# untitled.net
KiCad netlist of a schematic drawn in EAGLE
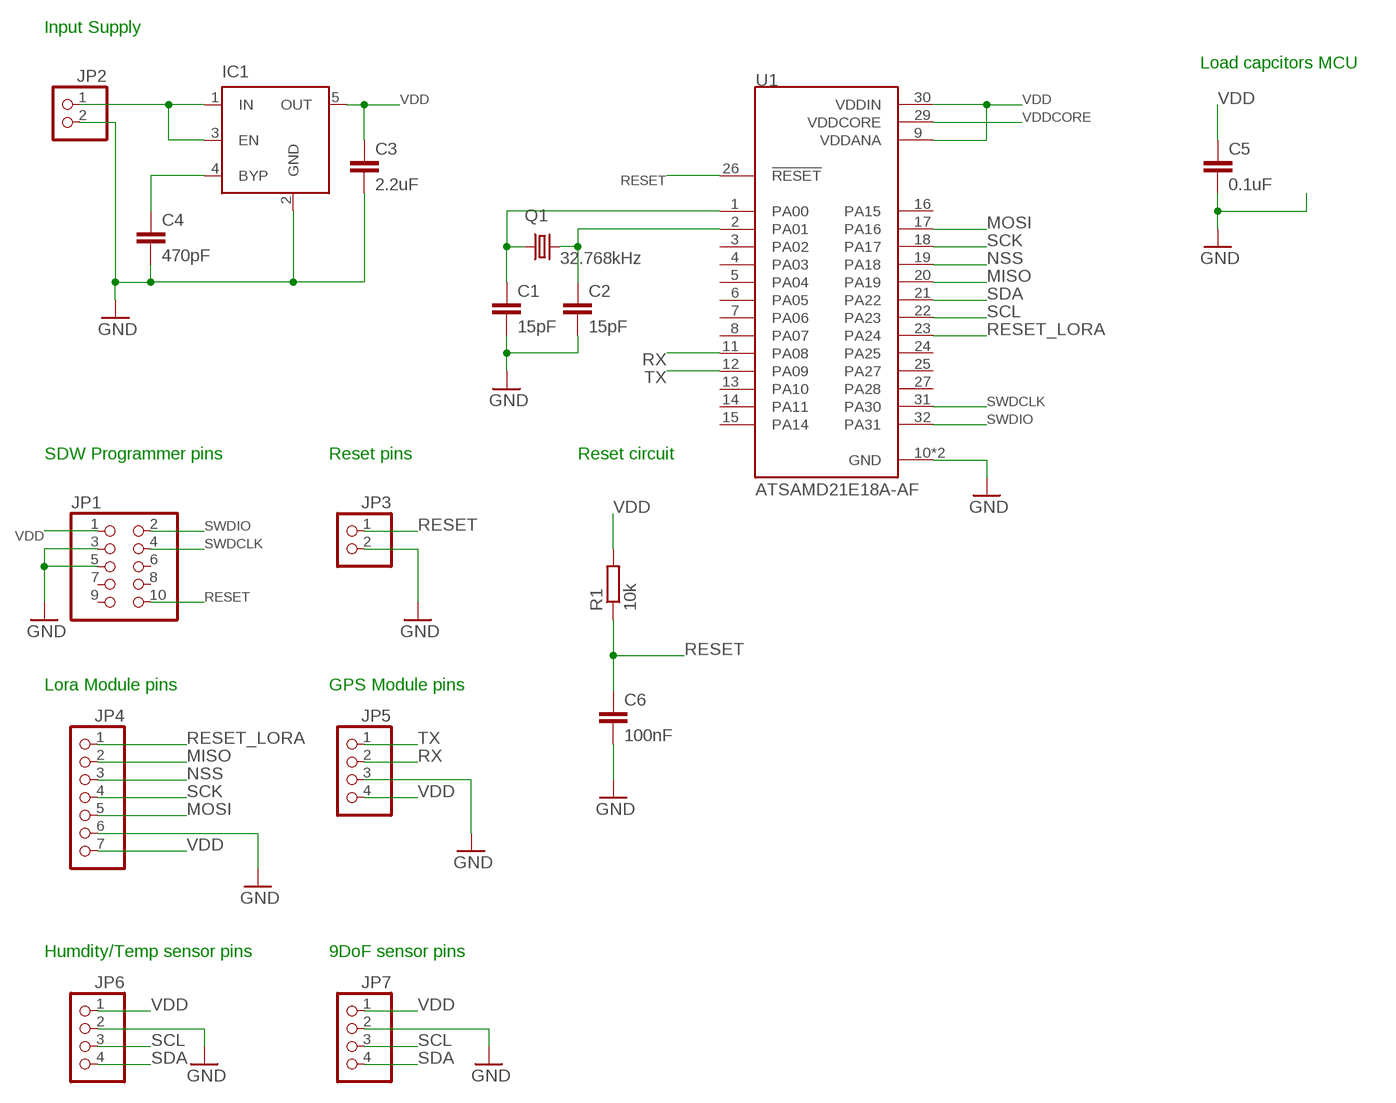
[diagram p0: schematic, sheet 1]

(export (version "E")
  (design (tool "Eeschema 10.0.6"))
  (components
    (comp (ref "C1")
      (value "15pF")
      (footprint "eagle-import:C0805")
      (libsource (lib "eagle-import") (part "C-EUC0805"))
    )
    (comp (ref "C2")
      (value "15pF")
      (footprint "eagle-import:C0805")
      (libsource (lib "eagle-import") (part "C-EUC0805"))
    )
    (comp (ref "C3")
      (value "2.2uF")
      (footprint "eagle-import:C0805")
      (libsource (lib "eagle-import") (part "C-EUC0805"))
    )
    (comp (ref "C4")
      (value "470pF")
      (footprint "eagle-import:C0805")
      (libsource (lib "eagle-import") (part "C-EUC0805"))
    )
    (comp (ref "C5")
      (value "0.1uF")
      (footprint "eagle-import:C0805")
      (libsource (lib "eagle-import") (part "C-EUC0805"))
    )
    (comp (ref "C6")
      (value "100nF")
      (footprint "eagle-import:C0805")
      (libsource (lib "eagle-import") (part "C-EUC0805"))
    )
    (comp (ref "IC1")
      (value "MIC5219XX")
      (footprint "eagle-import:SOT23-5")
      (libsource (lib "eagle-import") (part "MIC5219XX"))
    )
    (comp (ref "JP1")
      (value "PINHD-2X5")
      (footprint "eagle-import:2X05")
      (libsource (lib "eagle-import") (part "PINHD-2X5"))
    )
    (comp (ref "JP2")
      (value "PINHD-1X2")
      (footprint "eagle-import:1X02")
      (libsource (lib "eagle-import") (part "PINHD-1X2"))
    )
    (comp (ref "JP3")
      (value "PINHD-1X2")
      (footprint "eagle-import:1X02")
      (libsource (lib "eagle-import") (part "PINHD-1X2"))
    )
    (comp (ref "JP4")
      (value "PINHD-1X7")
      (footprint "eagle-import:1X07")
      (libsource (lib "eagle-import") (part "PINHD-1X7"))
    )
    (comp (ref "JP5")
      (value "PINHD-1X4")
      (footprint "eagle-import:1X04")
      (libsource (lib "eagle-import") (part "PINHD-1X4"))
    )
    (comp (ref "JP6")
      (value "PINHD-1X4")
      (footprint "eagle-import:1X04")
      (libsource (lib "eagle-import") (part "PINHD-1X4"))
    )
    (comp (ref "JP7")
      (value "PINHD-1X4")
      (footprint "eagle-import:1X04")
      (libsource (lib "eagle-import") (part "PINHD-1X4"))
    )
    (comp (ref "Q1")
      (value "32.768kHz")
      (footprint "eagle-import:CTS406")
      (libsource (lib "eagle-import") (part "CRYSTALCTS406"))
    )
    (comp (ref "R1")
      (value "10k")
      (footprint "eagle-import:R0805")
      (libsource (lib "eagle-import") (part "R-EU_R0805"))
    )
    (comp (ref "U1")
      (value "ATSAMD21E18A-AF")
      (footprint "eagle-import:QFP80P900X900X120-32N")
      (fields (field (name "MF") "Microchip"))
      (libsource (lib "eagle-import") (part "ATSAMD21E18A-AF"))
    )
  )
  (nets
    (net (code "1") (name "/MISO") (class "Default")
      (node (ref "JP4") (pin "2") (pinfunction "2_2") (pintype "passive"))
      (node (ref "U1") (pin "20") (pinfunction "PA19_20") (pintype "bidirectional"))
    )
    (net (code "2") (name "/MOSI") (class "Default")
      (node (ref "JP4") (pin "5") (pinfunction "5_5") (pintype "passive"))
      (node (ref "U1") (pin "17") (pinfunction "PA16_17") (pintype "bidirectional"))
    )
    (net (code "3") (name "/NSS") (class "Default")
      (node (ref "JP4") (pin "3") (pinfunction "3_3") (pintype "passive"))
      (node (ref "U1") (pin "19") (pinfunction "PA18_19") (pintype "bidirectional"))
    )
    (net (code "4") (name "/RESET") (class "Default")
      (node (ref "C6") (pin "1") (pinfunction "1_1") (pintype "passive"))
      (node (ref "JP1") (pin "10") (pinfunction "10_10") (pintype "passive"))
      (node (ref "JP3") (pin "1") (pinfunction "1_1") (pintype "passive"))
      (node (ref "R1") (pin "1") (pinfunction "1_1") (pintype "passive"))
      (node (ref "U1") (pin "26") (pinfunction "~{RESET}_26") (pintype "input"))
    )
    (net (code "5") (name "/RESET_LORA") (class "Default")
      (node (ref "JP4") (pin "1") (pinfunction "1_1") (pintype "passive"))
      (node (ref "U1") (pin "23") (pinfunction "PA24_23") (pintype "bidirectional"))
    )
    (net (code "6") (name "/RX") (class "Default")
      (node (ref "JP5") (pin "2") (pinfunction "2_2") (pintype "passive"))
      (node (ref "U1") (pin "11") (pinfunction "PA08_11") (pintype "bidirectional"))
    )
    (net (code "7") (name "/SCK") (class "Default")
      (node (ref "JP4") (pin "4") (pinfunction "4_4") (pintype "passive"))
      (node (ref "U1") (pin "18") (pinfunction "PA17_18") (pintype "bidirectional"))
    )
    (net (code "8") (name "/SCL") (class "Default")
      (node (ref "JP6") (pin "3") (pinfunction "3_3") (pintype "passive"))
      (node (ref "JP7") (pin "3") (pinfunction "3_3") (pintype "passive"))
      (node (ref "U1") (pin "22") (pinfunction "PA23_22") (pintype "bidirectional"))
    )
    (net (code "9") (name "/SDA") (class "Default")
      (node (ref "JP6") (pin "4") (pinfunction "4_4") (pintype "passive"))
      (node (ref "JP7") (pin "4") (pinfunction "4_4") (pintype "passive"))
      (node (ref "U1") (pin "21") (pinfunction "PA22_21") (pintype "bidirectional"))
    )
    (net (code "10") (name "/SWDCLK") (class "Default")
      (node (ref "JP1") (pin "4") (pinfunction "4_4") (pintype "passive"))
      (node (ref "U1") (pin "31") (pinfunction "PA30_31") (pintype "bidirectional"))
    )
    (net (code "11") (name "/SWDIO") (class "Default")
      (node (ref "JP1") (pin "2") (pinfunction "2_2") (pintype "passive"))
      (node (ref "U1") (pin "32") (pinfunction "PA31_32") (pintype "bidirectional"))
    )
    (net (code "12") (name "/TX") (class "Default")
      (node (ref "JP5") (pin "1") (pinfunction "1_1") (pintype "passive"))
      (node (ref "U1") (pin "12") (pinfunction "PA09_12") (pintype "bidirectional"))
    )
    (net (code "13") (name "/VDD") (class "Default")
      (node (ref "C3") (pin "1") (pinfunction "1_1") (pintype "passive"))
      (node (ref "C5") (pin "1") (pinfunction "1_1") (pintype "passive"))
      (node (ref "IC1") (pin "5") (pinfunction "OUT_5") (pintype "output"))
      (node (ref "JP1") (pin "1") (pinfunction "1_1") (pintype "passive"))
      (node (ref "JP4") (pin "7") (pinfunction "7_7") (pintype "passive"))
      (node (ref "JP5") (pin "4") (pinfunction "4_4") (pintype "passive"))
      (node (ref "JP6") (pin "1") (pinfunction "1_1") (pintype "passive"))
      (node (ref "JP7") (pin "1") (pinfunction "1_1") (pintype "passive"))
      (node (ref "R1") (pin "2") (pinfunction "2_2") (pintype "passive"))
      (node (ref "U1") (pin "30") (pinfunction "VDDIN_30") (pintype "power_in"))
      (node (ref "U1") (pin "9") (pinfunction "VDDANA_9") (pintype "power_in"))
    )
    (net (code "14") (name "/VDDCORE") (class "Default")
      (node (ref "U1") (pin "29") (pinfunction "VDDCORE_29") (pintype "power_in"))
    )
    (net (code "15") (name "GND") (class "Default")
      (node (ref "C1") (pin "2") (pinfunction "2_2") (pintype "passive"))
      (node (ref "C2") (pin "2") (pinfunction "2_2") (pintype "passive"))
      (node (ref "C3") (pin "2") (pinfunction "2_2") (pintype "passive"))
      (node (ref "C4") (pin "2") (pinfunction "2_2") (pintype "passive"))
      (node (ref "C5") (pin "2") (pinfunction "2_2") (pintype "passive"))
      (node (ref "C6") (pin "2") (pinfunction "2_2") (pintype "passive"))
      (node (ref "IC1") (pin "2") (pinfunction "GND_2") (pintype "power_in"))
      (node (ref "JP1") (pin "3") (pinfunction "3_3") (pintype "passive"))
      (node (ref "JP1") (pin "5") (pinfunction "5_5") (pintype "passive"))
      (node (ref "JP2") (pin "2") (pinfunction "2_2") (pintype "passive"))
      (node (ref "JP3") (pin "2") (pinfunction "2_2") (pintype "passive"))
      (node (ref "JP4") (pin "6") (pinfunction "6_6") (pintype "passive"))
      (node (ref "JP5") (pin "3") (pinfunction "3_3") (pintype "passive"))
      (node (ref "JP6") (pin "2") (pinfunction "2_2") (pintype "passive"))
      (node (ref "JP7") (pin "2") (pinfunction "2_2") (pintype "passive"))
      (node (ref "U1") (pin "10") (pinfunction "GND_10") (pintype "power_in"))
      (node (ref "U1") (pin "28") (pinfunction "GND_28") (pintype "power_in"))
    )
    (net (code "16") (name "Net-(IC1-BYP)") (class "Default")
      (node (ref "C4") (pin "1") (pinfunction "1_1") (pintype "passive"))
      (node (ref "IC1") (pin "4") (pinfunction "BYP_4") (pintype "passive"))
    )
    (net (code "17") (name "Net-(IC1-EN)") (class "Default")
      (node (ref "IC1") (pin "1") (pinfunction "IN_1") (pintype "input"))
      (node (ref "IC1") (pin "3") (pinfunction "EN_3") (pintype "input"))
      (node (ref "JP2") (pin "1") (pinfunction "1_1") (pintype "passive"))
    )
    (net (code "18") (name "Net-(Q1-2)") (class "Default")
      (node (ref "C2") (pin "1") (pinfunction "1_1") (pintype "passive"))
      (node (ref "Q1") (pin "3") (pinfunction "2_3") (pintype "passive"))
      (node (ref "U1") (pin "2") (pinfunction "PA01_2") (pintype "bidirectional"))
    )
    (net (code "19") (name "Net-(U1-PA00)") (class "Default")
      (node (ref "C1") (pin "1") (pinfunction "1_1") (pintype "passive"))
      (node (ref "Q1") (pin "1") (pinfunction "1_1") (pintype "passive"))
      (node (ref "U1") (pin "1") (pinfunction "PA00_1") (pintype "bidirectional"))
    )
    (net (code "20") (name "unconnected-(JP1-Pad6)") (class "Default")
      (node (ref "JP1") (pin "6") (pinfunction "6_6") (pintype "passive"))
    )
    (net (code "21") (name "unconnected-(JP1-Pad7)") (class "Default")
      (node (ref "JP1") (pin "7") (pinfunction "7_7") (pintype "passive"))
    )
    (net (code "22") (name "unconnected-(JP1-Pad8)") (class "Default")
      (node (ref "JP1") (pin "8") (pinfunction "8_8") (pintype "passive"))
    )
    (net (code "23") (name "unconnected-(JP1-Pad9)") (class "Default")
      (node (ref "JP1") (pin "9") (pinfunction "9_9") (pintype "passive"))
    )
    (net (code "24") (name "unconnected-(U1-PA02-Pad3)") (class "Default")
      (node (ref "U1") (pin "3") (pinfunction "PA02_3") (pintype "bidirectional"))
    )
    (net (code "25") (name "unconnected-(U1-PA03-Pad4)") (class "Default")
      (node (ref "U1") (pin "4") (pinfunction "PA03_4") (pintype "bidirectional"))
    )
    (net (code "26") (name "unconnected-(U1-PA04-Pad5)") (class "Default")
      (node (ref "U1") (pin "5") (pinfunction "PA04_5") (pintype "bidirectional"))
    )
    (net (code "27") (name "unconnected-(U1-PA05-Pad6)") (class "Default")
      (node (ref "U1") (pin "6") (pinfunction "PA05_6") (pintype "bidirectional"))
    )
    (net (code "28") (name "unconnected-(U1-PA06-Pad7)") (class "Default")
      (node (ref "U1") (pin "7") (pinfunction "PA06_7") (pintype "bidirectional"))
    )
    (net (code "29") (name "unconnected-(U1-PA07-Pad8)") (class "Default")
      (node (ref "U1") (pin "8") (pinfunction "PA07_8") (pintype "bidirectional"))
    )
    (net (code "30") (name "unconnected-(U1-PA10-Pad13)") (class "Default")
      (node (ref "U1") (pin "13") (pinfunction "PA10_13") (pintype "bidirectional"))
    )
    (net (code "31") (name "unconnected-(U1-PA11-Pad14)") (class "Default")
      (node (ref "U1") (pin "14") (pinfunction "PA11_14") (pintype "bidirectional"))
    )
    (net (code "32") (name "unconnected-(U1-PA14-Pad15)") (class "Default")
      (node (ref "U1") (pin "15") (pinfunction "PA14_15") (pintype "bidirectional"))
    )
    (net (code "33") (name "unconnected-(U1-PA15-Pad16)") (class "Default")
      (node (ref "U1") (pin "16") (pinfunction "PA15_16") (pintype "bidirectional"))
    )
    (net (code "34") (name "unconnected-(U1-PA25-Pad24)") (class "Default")
      (node (ref "U1") (pin "24") (pinfunction "PA25_24") (pintype "bidirectional"))
    )
    (net (code "35") (name "unconnected-(U1-PA27-Pad25)") (class "Default")
      (node (ref "U1") (pin "25") (pinfunction "PA27_25") (pintype "bidirectional"))
    )
    (net (code "36") (name "unconnected-(U1-PA28-Pad27)") (class "Default")
      (node (ref "U1") (pin "27") (pinfunction "PA28_27") (pintype "bidirectional"))
    )
  )
)
